# Block_M.net
KiCad netlist of a schematic drawn in EAGLE
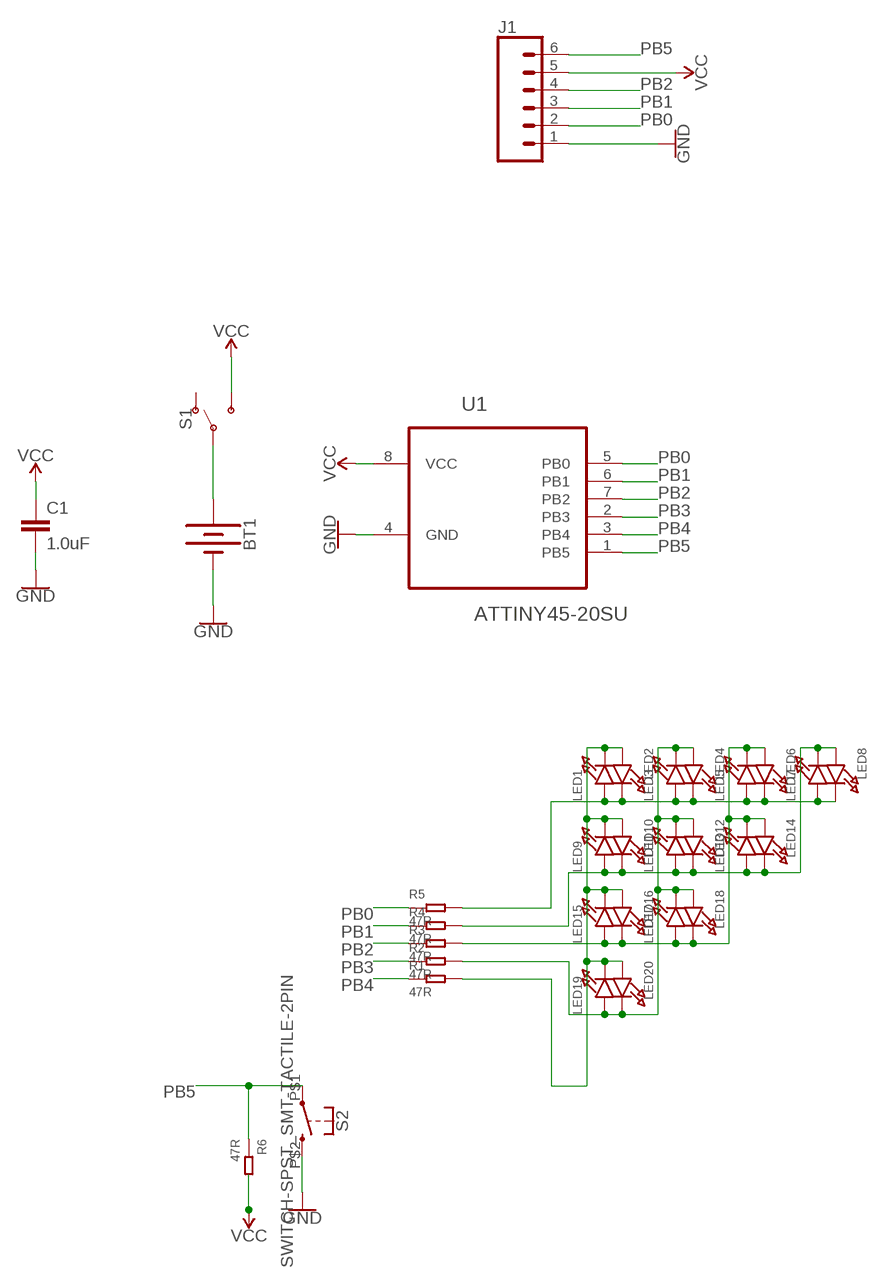
[diagram p0: schematic, sheet 1]

(export (version "E")
  (design (tool "Eeschema 10.0.6"))
  (components
    (comp (ref "BT1")
      (value "BATTERY-12MM_SMD_ALT")
      (footprint "eagle-import:BATTCON_12MM_ALT")
      (libsource (lib "eagle-import") (part "BATTERY-12MM_SMD_ALT"))
    )
    (comp (ref "C1")
      (value "1.0uF")
      (footprint "eagle-import:0805")
      (libsource (lib "eagle-import") (part "1.0UF-0805-25V-10%"))
    )
    (comp (ref "J1")
      (value "CONN_06SMD-FEMALE-NO-SILK")
      (footprint "eagle-import:1X06-SMD-FEMALE_NO_SILK")
      (libsource (lib "eagle-import") (part "CONN_06SMD-FEMALE-NO-SILK"))
    )
    (comp (ref "LED1")
      (value "LED0805_NOOUTLINE")
      (footprint "eagle-import:CHIPLED_0805_NOOUTLINE")
      (libsource (lib "eagle-import") (part "LED0805_NOOUTLINE"))
    )
    (comp (ref "LED2")
      (value "LED0805_NOOUTLINE")
      (footprint "eagle-import:CHIPLED_0805_NOOUTLINE")
      (libsource (lib "eagle-import") (part "LED0805_NOOUTLINE"))
    )
    (comp (ref "LED3")
      (value "LED0805_NOOUTLINE")
      (footprint "eagle-import:CHIPLED_0805_NOOUTLINE")
      (libsource (lib "eagle-import") (part "LED0805_NOOUTLINE"))
    )
    (comp (ref "LED4")
      (value "LED0805_NOOUTLINE")
      (footprint "eagle-import:CHIPLED_0805_NOOUTLINE")
      (libsource (lib "eagle-import") (part "LED0805_NOOUTLINE"))
    )
    (comp (ref "LED5")
      (value "LED0805_NOOUTLINE")
      (footprint "eagle-import:CHIPLED_0805_NOOUTLINE")
      (libsource (lib "eagle-import") (part "LED0805_NOOUTLINE"))
    )
    (comp (ref "LED6")
      (value "LED0805_NOOUTLINE")
      (footprint "eagle-import:CHIPLED_0805_NOOUTLINE")
      (libsource (lib "eagle-import") (part "LED0805_NOOUTLINE"))
    )
    (comp (ref "LED7")
      (value "LED0805_NOOUTLINE")
      (footprint "eagle-import:CHIPLED_0805_NOOUTLINE")
      (libsource (lib "eagle-import") (part "LED0805_NOOUTLINE"))
    )
    (comp (ref "LED8")
      (value "LED0805_NOOUTLINE")
      (footprint "eagle-import:CHIPLED_0805_NOOUTLINE")
      (libsource (lib "eagle-import") (part "LED0805_NOOUTLINE"))
    )
    (comp (ref "LED9")
      (value "LED0805_NOOUTLINE")
      (footprint "eagle-import:CHIPLED_0805_NOOUTLINE")
      (libsource (lib "eagle-import") (part "LED0805_NOOUTLINE"))
    )
    (comp (ref "LED10")
      (value "LED0805_NOOUTLINE")
      (footprint "eagle-import:CHIPLED_0805_NOOUTLINE")
      (libsource (lib "eagle-import") (part "LED0805_NOOUTLINE"))
    )
    (comp (ref "LED11")
      (value "LED0805_NOOUTLINE")
      (footprint "eagle-import:CHIPLED_0805_NOOUTLINE")
      (libsource (lib "eagle-import") (part "LED0805_NOOUTLINE"))
    )
    (comp (ref "LED12")
      (value "LED0805_NOOUTLINE")
      (footprint "eagle-import:CHIPLED_0805_NOOUTLINE")
      (libsource (lib "eagle-import") (part "LED0805_NOOUTLINE"))
    )
    (comp (ref "LED13")
      (value "LED0805_NOOUTLINE")
      (footprint "eagle-import:CHIPLED_0805_NOOUTLINE")
      (libsource (lib "eagle-import") (part "LED0805_NOOUTLINE"))
    )
    (comp (ref "LED14")
      (value "LED0805_NOOUTLINE")
      (footprint "eagle-import:CHIPLED_0805_NOOUTLINE")
      (libsource (lib "eagle-import") (part "LED0805_NOOUTLINE"))
    )
    (comp (ref "LED15")
      (value "LED0805_NOOUTLINE")
      (footprint "eagle-import:CHIPLED_0805_NOOUTLINE")
      (libsource (lib "eagle-import") (part "LED0805_NOOUTLINE"))
    )
    (comp (ref "LED16")
      (value "LED0805_NOOUTLINE")
      (footprint "eagle-import:CHIPLED_0805_NOOUTLINE")
      (libsource (lib "eagle-import") (part "LED0805_NOOUTLINE"))
    )
    (comp (ref "LED17")
      (value "LED0805_NOOUTLINE")
      (footprint "eagle-import:CHIPLED_0805_NOOUTLINE")
      (libsource (lib "eagle-import") (part "LED0805_NOOUTLINE"))
    )
    (comp (ref "LED18")
      (value "LED0805_NOOUTLINE")
      (footprint "eagle-import:CHIPLED_0805_NOOUTLINE")
      (libsource (lib "eagle-import") (part "LED0805_NOOUTLINE"))
    )
    (comp (ref "LED19")
      (value "LED0805_NOOUTLINE")
      (footprint "eagle-import:CHIPLED_0805_NOOUTLINE")
      (libsource (lib "eagle-import") (part "LED0805_NOOUTLINE"))
    )
    (comp (ref "LED20")
      (value "LED0805_NOOUTLINE")
      (footprint "eagle-import:CHIPLED_0805_NOOUTLINE")
      (libsource (lib "eagle-import") (part "LED0805_NOOUTLINE"))
    )
    (comp (ref "R1")
      (value "47R")
      (footprint "eagle-import:R0805")
      (fields (field (name "MPN") "RC0805JR-0747RL"))
      (libsource (lib "eagle-import") (part "SMD-RES-47R-5%-1/8W(0805)"))
    )
    (comp (ref "R2")
      (value "47R")
      (footprint "eagle-import:R0805")
      (fields (field (name "MPN") "RC0805JR-0747RL"))
      (libsource (lib "eagle-import") (part "SMD-RES-47R-5%-1/8W(0805)"))
    )
    (comp (ref "R3")
      (value "47R")
      (footprint "eagle-import:R0805")
      (fields (field (name "MPN") "RC0805JR-0747RL"))
      (libsource (lib "eagle-import") (part "SMD-RES-47R-5%-1/8W(0805)"))
    )
    (comp (ref "R4")
      (value "47R")
      (footprint "eagle-import:R0805")
      (fields (field (name "MPN") "RC0805JR-0747RL"))
      (libsource (lib "eagle-import") (part "SMD-RES-47R-5%-1/8W(0805)"))
    )
    (comp (ref "R5")
      (value "47R")
      (footprint "eagle-import:R0805")
      (fields (field (name "MPN") "RC0805JR-0747RL"))
      (libsource (lib "eagle-import") (part "SMD-RES-47R-5%-1/8W(0805)"))
    )
    (comp (ref "R6")
      (value "47R")
      (footprint "eagle-import:R0805")
      (fields (field (name "MPN") "RC0805JR-0747RL"))
      (libsource (lib "eagle-import") (part "SMD-RES-47R-5%-1/8W(0805)"))
    )
    (comp (ref "S1")
      (value "SWITCH-SPDT-SMD-RIGHT-ANGLE")
      (footprint "eagle-import:SWITCH_SPST_SMD_A")
      (libsource (lib "eagle-import") (part "SWITCH-SPDT-SMD-RIGHT-ANGLE"))
    )
    (comp (ref "S2")
      (value "SWITCH-SPST_SMT-TACTILE-2PIN")
      (footprint "eagle-import:SMT_TACTILE_SWITCH_3X2MM")
      (libsource (lib "eagle-import") (part "SWITCH-SPST_SMT-TACTILE-2PIN"))
    )
    (comp (ref "U1")
      (value "ATTINY45-20SU")
      (footprint "eagle-import:SOIC127P798X216-8N")
      (libsource (lib "eagle-import") (part "ATTINY45-20SU"))
    )
  )
  (nets
    (net (code "1") (name "/PB0") (class "Default")
      (node (ref "J1") (pin "2") (pinfunction "2_2") (pintype "passive"))
      (node (ref "R5") (pin "1") (pinfunction "1_1") (pintype "passive"))
      (node (ref "U1") (pin "5") (pinfunction "PB0_5") (pintype "bidirectional"))
    )
    (net (code "2") (name "/PB1") (class "Default")
      (node (ref "J1") (pin "3") (pinfunction "3_3") (pintype "passive"))
      (node (ref "R4") (pin "1") (pinfunction "1_1") (pintype "passive"))
      (node (ref "U1") (pin "6") (pinfunction "PB1_6") (pintype "bidirectional"))
    )
    (net (code "3") (name "/PB2") (class "Default")
      (node (ref "J1") (pin "4") (pinfunction "4_4") (pintype "passive"))
      (node (ref "R3") (pin "1") (pinfunction "1_1") (pintype "passive"))
      (node (ref "U1") (pin "7") (pinfunction "PB2_7") (pintype "bidirectional"))
    )
    (net (code "4") (name "/PB3") (class "Default")
      (node (ref "R2") (pin "1") (pinfunction "1_1") (pintype "passive"))
      (node (ref "U1") (pin "2") (pinfunction "PB3_2") (pintype "bidirectional"))
    )
    (net (code "5") (name "/PB4") (class "Default")
      (node (ref "R1") (pin "1") (pinfunction "1_1") (pintype "passive"))
      (node (ref "U1") (pin "3") (pinfunction "PB4_3") (pintype "bidirectional"))
    )
    (net (code "6") (name "/PB5") (class "Default")
      (node (ref "J1") (pin "6") (pinfunction "6_6") (pintype "passive"))
      (node (ref "R6") (pin "1") (pinfunction "1_1") (pintype "passive"))
      (node (ref "S2") (pin "P$1") (pinfunction "1_P$1") (pintype "passive"))
      (node (ref "U1") (pin "1") (pinfunction "PB5_1") (pintype "bidirectional"))
    )
    (net (code "7") (name "GND") (class "Default")
      (node (ref "BT1") (pin "GND") (pinfunction "-_GND") (pintype "power_in"))
      (node (ref "C1") (pin "2") (pinfunction "2_2") (pintype "passive"))
      (node (ref "J1") (pin "1") (pinfunction "1_1") (pintype "passive"))
      (node (ref "S2") (pin "P$2") (pinfunction "2_P$2") (pintype "passive"))
      (node (ref "U1") (pin "4") (pinfunction "GND_4") (pintype "passive"))
    )
    (net (code "8") (name "Net-(BT1-+)") (class "Default")
      (node (ref "BT1") (pin "PWR@2") (pinfunction "+_PWR@2") (pintype "power_in"))
      (node (ref "S1") (pin "2") (pinfunction "P_2") (pintype "passive"))
    )
    (net (code "9") (name "Net-(LED1-PadA)") (class "Default")
      (node (ref "LED1") (pin "A") (pinfunction "A_A") (pintype "passive"))
      (node (ref "LED2") (pin "C") (pinfunction "C_C") (pintype "passive"))
      (node (ref "LED3") (pin "A") (pinfunction "A_A") (pintype "passive"))
      (node (ref "LED4") (pin "C") (pinfunction "C_C") (pintype "passive"))
      (node (ref "LED5") (pin "A") (pinfunction "A_A") (pintype "passive"))
      (node (ref "LED6") (pin "C") (pinfunction "C_C") (pintype "passive"))
      (node (ref "LED7") (pin "A") (pinfunction "A_A") (pintype "passive"))
      (node (ref "LED8") (pin "C") (pinfunction "C_C") (pintype "passive"))
      (node (ref "R5") (pin "2") (pinfunction "2_2") (pintype "passive"))
    )
    (net (code "10") (name "Net-(LED1-PadC)") (class "Default")
      (node (ref "LED1") (pin "C") (pinfunction "C_C") (pintype "passive"))
      (node (ref "LED10") (pin "A") (pinfunction "A_A") (pintype "passive"))
      (node (ref "LED15") (pin "C") (pinfunction "C_C") (pintype "passive"))
      (node (ref "LED16") (pin "A") (pinfunction "A_A") (pintype "passive"))
      (node (ref "LED19") (pin "C") (pinfunction "C_C") (pintype "passive"))
      (node (ref "LED2") (pin "A") (pinfunction "A_A") (pintype "passive"))
      (node (ref "LED20") (pin "A") (pinfunction "A_A") (pintype "passive"))
      (node (ref "LED9") (pin "C") (pinfunction "C_C") (pintype "passive"))
      (node (ref "R1") (pin "2") (pinfunction "2_2") (pintype "passive"))
    )
    (net (code "11") (name "Net-(LED10-PadC)") (class "Default")
      (node (ref "LED10") (pin "C") (pinfunction "C_C") (pintype "passive"))
      (node (ref "LED11") (pin "A") (pinfunction "A_A") (pintype "passive"))
      (node (ref "LED12") (pin "C") (pinfunction "C_C") (pintype "passive"))
      (node (ref "LED13") (pin "A") (pinfunction "A_A") (pintype "passive"))
      (node (ref "LED14") (pin "C") (pinfunction "C_C") (pintype "passive"))
      (node (ref "LED7") (pin "C") (pinfunction "C_C") (pintype "passive"))
      (node (ref "LED8") (pin "A") (pinfunction "A_A") (pintype "passive"))
      (node (ref "LED9") (pin "A") (pinfunction "A_A") (pintype "passive"))
      (node (ref "R4") (pin "2") (pinfunction "2_2") (pintype "passive"))
    )
    (net (code "12") (name "Net-(LED11-PadC)") (class "Default")
      (node (ref "LED11") (pin "C") (pinfunction "C_C") (pintype "passive"))
      (node (ref "LED12") (pin "A") (pinfunction "A_A") (pintype "passive"))
      (node (ref "LED17") (pin "C") (pinfunction "C_C") (pintype "passive"))
      (node (ref "LED18") (pin "A") (pinfunction "A_A") (pintype "passive"))
      (node (ref "LED19") (pin "A") (pinfunction "A_A") (pintype "passive"))
      (node (ref "LED20") (pin "C") (pinfunction "C_C") (pintype "passive"))
      (node (ref "LED3") (pin "C") (pinfunction "C_C") (pintype "passive"))
      (node (ref "LED4") (pin "A") (pinfunction "A_A") (pintype "passive"))
      (node (ref "R2") (pin "2") (pinfunction "2_2") (pintype "passive"))
    )
    (net (code "13") (name "Net-(LED13-PadC)") (class "Default")
      (node (ref "LED13") (pin "C") (pinfunction "C_C") (pintype "passive"))
      (node (ref "LED14") (pin "A") (pinfunction "A_A") (pintype "passive"))
      (node (ref "LED15") (pin "A") (pinfunction "A_A") (pintype "passive"))
      (node (ref "LED16") (pin "C") (pinfunction "C_C") (pintype "passive"))
      (node (ref "LED17") (pin "A") (pinfunction "A_A") (pintype "passive"))
      (node (ref "LED18") (pin "C") (pinfunction "C_C") (pintype "passive"))
      (node (ref "LED5") (pin "C") (pinfunction "C_C") (pintype "passive"))
      (node (ref "LED6") (pin "A") (pinfunction "A_A") (pintype "passive"))
      (node (ref "R3") (pin "2") (pinfunction "2_2") (pintype "passive"))
    )
    (net (code "14") (name "VCC") (class "Default")
      (node (ref "C1") (pin "1") (pinfunction "1_1") (pintype "passive"))
      (node (ref "J1") (pin "5") (pinfunction "5_5") (pintype "passive"))
      (node (ref "R6") (pin "2") (pinfunction "2_2") (pintype "passive"))
      (node (ref "S1") (pin "3") (pinfunction "S_3") (pintype "passive"))
      (node (ref "U1") (pin "8") (pinfunction "VCC_8") (pintype "power_in"))
    )
    (net (code "15") (name "unconnected-(S1-O-Pad1)") (class "Default")
      (node (ref "S1") (pin "1") (pinfunction "O_1") (pintype "passive"))
    )
  )
)
